# IsNoTeensy_v1_0.net
KiCad netlist of a schematic drawn in EAGLE
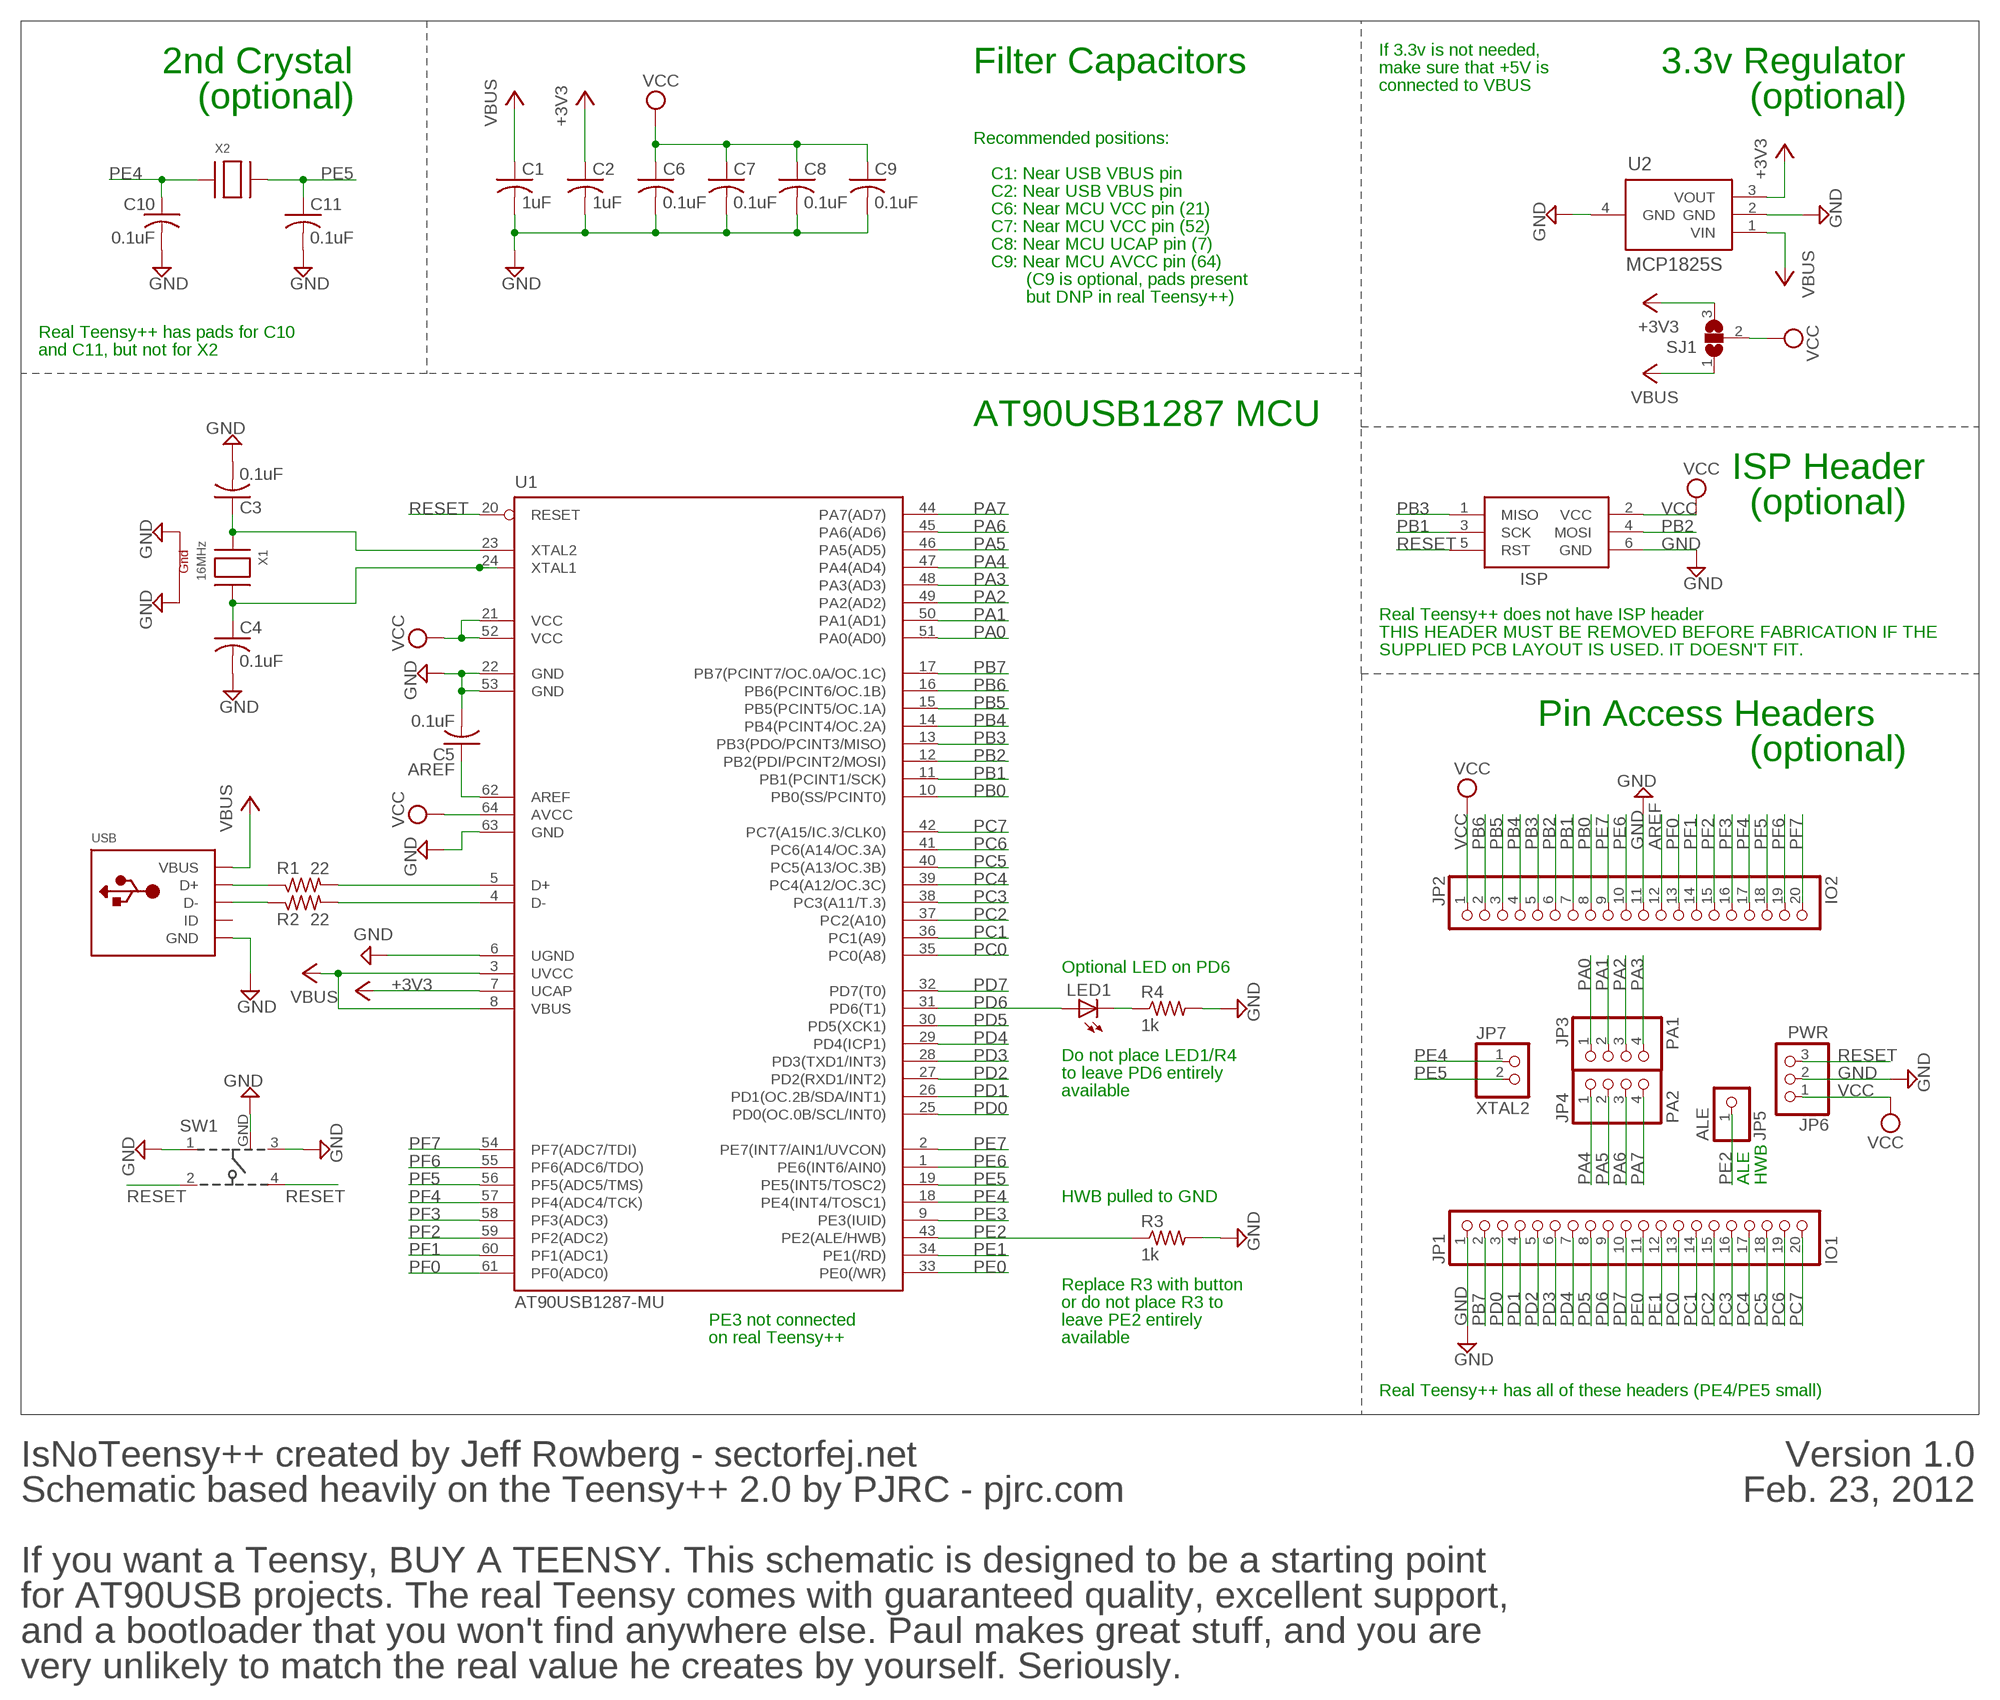
[diagram p0: schematic, sheet 1]

(export (version "E")
  (design (tool "Eeschema 10.0.6"))
  (components
    (comp (ref "C1")
      (value "1uF")
      (footprint "eagle-import:C0603")
      (libsource (lib "eagle-import") (part "C-USC0603"))
    )
    (comp (ref "C2")
      (value "1uF")
      (footprint "eagle-import:C0603")
      (libsource (lib "eagle-import") (part "C-USC0603"))
    )
    (comp (ref "C3")
      (value "0.1uF")
      (footprint "eagle-import:C0402")
      (libsource (lib "eagle-import") (part "C-USC0402"))
    )
    (comp (ref "C4")
      (value "0.1uF")
      (footprint "eagle-import:C0402")
      (libsource (lib "eagle-import") (part "C-USC0402"))
    )
    (comp (ref "C5")
      (value "0.1uF")
      (footprint "eagle-import:C0402")
      (libsource (lib "eagle-import") (part "C-USC0402"))
    )
    (comp (ref "C6")
      (value "0.1uF")
      (footprint "eagle-import:C0402")
      (libsource (lib "eagle-import") (part "C-USC0402"))
    )
    (comp (ref "C7")
      (value "0.1uF")
      (footprint "eagle-import:C0402")
      (libsource (lib "eagle-import") (part "C-USC0402"))
    )
    (comp (ref "C8")
      (value "0.1uF")
      (footprint "eagle-import:C0402")
      (libsource (lib "eagle-import") (part "C-USC0402"))
    )
    (comp (ref "C9")
      (value "0.1uF")
      (footprint "eagle-import:C0805")
      (libsource (lib "eagle-import") (part "C-USC0805"))
    )
    (comp (ref "C10")
      (value "0.1uF")
      (footprint "eagle-import:C0805")
      (libsource (lib "eagle-import") (part "C-USC0805"))
    )
    (comp (ref "C11")
      (value "0.1uF")
      (footprint "eagle-import:C0805")
      (libsource (lib "eagle-import") (part "C-USC0805"))
    )
    (comp (ref "ISP")
      (value "AVRISP-6")
      (footprint "eagle-import:AVRISP")
      (libsource (lib "eagle-import") (part "AVRISP-6"))
    )
    (comp (ref "JP1")
      (value "IO1")
      (footprint "eagle-import:1X20")
      (libsource (lib "eagle-import") (part "PINHD-1X20"))
    )
    (comp (ref "JP2")
      (value "IO2")
      (footprint "eagle-import:1X20")
      (libsource (lib "eagle-import") (part "PINHD-1X20"))
    )
    (comp (ref "JP3")
      (value "PA1")
      (footprint "eagle-import:1X04")
      (libsource (lib "eagle-import") (part "PINHD-1X4"))
    )
    (comp (ref "JP4")
      (value "PA2")
      (footprint "eagle-import:1X04")
      (libsource (lib "eagle-import") (part "PINHD-1X4"))
    )
    (comp (ref "JP5")
      (value "ALE")
      (footprint "eagle-import:1X01")
      (libsource (lib "eagle-import") (part "PINHD-1X1"))
    )
    (comp (ref "JP6")
      (value "PWR")
      (footprint "eagle-import:1X03")
      (libsource (lib "eagle-import") (part "PINHD-1X3"))
    )
    (comp (ref "JP7")
      (value "XTAL2")
      (footprint "eagle-import:1X02")
      (libsource (lib "eagle-import") (part "PINHD-1X2"))
    )
    (comp (ref "LED1")
      (value "LEDCHIP-LED0603")
      (footprint "eagle-import:CHIP-LED0603")
      (libsource (lib "eagle-import") (part "LEDCHIP-LED0603"))
    )
    (comp (ref "R1")
      (value "22")
      (footprint "eagle-import:R0402")
      (libsource (lib "eagle-import") (part "R-US_R0402"))
    )
    (comp (ref "R2")
      (value "22")
      (footprint "eagle-import:R0402")
      (libsource (lib "eagle-import") (part "R-US_R0402"))
    )
    (comp (ref "R3")
      (value "1k")
      (footprint "eagle-import:R0402")
      (libsource (lib "eagle-import") (part "R-US_R0402"))
    )
    (comp (ref "R4")
      (value "1k")
      (footprint "eagle-import:R0402")
      (libsource (lib "eagle-import") (part "R-US_R0402"))
    )
    (comp (ref "SJ1")
      (value "SJ2W")
      (footprint "eagle-import:SJ_2")
      (libsource (lib "eagle-import") (part "SJ2W"))
    )
    (comp (ref "SW1")
      (value "101-IG")
      (footprint "eagle-import:101-IG")
      (libsource (lib "eagle-import") (part "101-IG"))
    )
    (comp (ref "U1")
      (value "AT90USB1287-MU")
      (footprint "eagle-import:MLF64")
      (libsource (lib "eagle-import") (part "AT90USB1287-MU"))
    )
    (comp (ref "U2")
      (value "MCP1825S")
      (footprint "eagle-import:SOT223")
      (libsource (lib "eagle-import") (part "MCP1825S"))
    )
    (comp (ref "USB")
      (value "USBMINIB")
      (footprint "eagle-import:USB-MINIB")
      (libsource (lib "eagle-import") (part "USBMINIB"))
    )
    (comp (ref "X1")
      (value "16MHz")
      (footprint "eagle-import:NX3225")
      (libsource (lib "eagle-import") (part "XTAL-4-3225"))
    )
    (comp (ref "X2")
      (value "XTAL-3.2X1.5")
      (footprint "eagle-import:XTAL3215")
      (libsource (lib "eagle-import") (part "XTAL-3.2X1.5"))
    )
  )
  (nets
    (net (code "1") (name "+3V3") (class "Default")
      (node (ref "C2") (pin "1") (pinfunction "1_1") (pintype "passive"))
      (node (ref "SJ1") (pin "3") (pinfunction "3_3") (pintype "passive"))
      (node (ref "U1") (pin "7") (pinfunction "UCAP_7") (pintype "power_in"))
      (node (ref "U2") (pin "3") (pinfunction "VOUT_3") (pintype "power_in"))
    )
    (net (code "2") (name "/AREF") (class "Default")
      (node (ref "C5") (pin "1") (pinfunction "1_1") (pintype "passive"))
      (node (ref "JP2") (pin "12") (pinfunction "12_12") (pintype "passive"))
      (node (ref "U1") (pin "62") (pinfunction "AREF_62") (pintype "bidirectional"))
    )
    (net (code "3") (name "/PA0") (class "Default")
      (node (ref "JP3") (pin "1") (pinfunction "1_1") (pintype "passive"))
      (node (ref "U1") (pin "51") (pinfunction "PA0(AD0)_51") (pintype "bidirectional"))
    )
    (net (code "4") (name "/PA1") (class "Default")
      (node (ref "JP3") (pin "2") (pinfunction "2_2") (pintype "passive"))
      (node (ref "U1") (pin "50") (pinfunction "PA1(AD1)_50") (pintype "bidirectional"))
    )
    (net (code "5") (name "/PA2") (class "Default")
      (node (ref "JP3") (pin "3") (pinfunction "3_3") (pintype "passive"))
      (node (ref "U1") (pin "49") (pinfunction "PA2(AD2)_49") (pintype "bidirectional"))
    )
    (net (code "6") (name "/PA3") (class "Default")
      (node (ref "JP3") (pin "4") (pinfunction "4_4") (pintype "passive"))
      (node (ref "U1") (pin "48") (pinfunction "PA3(AD3)_48") (pintype "bidirectional"))
    )
    (net (code "7") (name "/PA4") (class "Default")
      (node (ref "JP4") (pin "1") (pinfunction "1_1") (pintype "passive"))
      (node (ref "U1") (pin "47") (pinfunction "PA4(AD4)_47") (pintype "bidirectional"))
    )
    (net (code "8") (name "/PA5") (class "Default")
      (node (ref "JP4") (pin "2") (pinfunction "2_2") (pintype "passive"))
      (node (ref "U1") (pin "46") (pinfunction "PA5(AD5)_46") (pintype "bidirectional"))
    )
    (net (code "9") (name "/PA6") (class "Default")
      (node (ref "JP4") (pin "3") (pinfunction "3_3") (pintype "passive"))
      (node (ref "U1") (pin "45") (pinfunction "PA6(AD6)_45") (pintype "bidirectional"))
    )
    (net (code "10") (name "/PA7") (class "Default")
      (node (ref "JP4") (pin "4") (pinfunction "4_4") (pintype "passive"))
      (node (ref "U1") (pin "44") (pinfunction "PA7(AD7)_44") (pintype "bidirectional"))
    )
    (net (code "11") (name "/PB0") (class "Default")
      (node (ref "JP2") (pin "8") (pinfunction "8_8") (pintype "passive"))
      (node (ref "U1") (pin "10") (pinfunction "PB0(SS/PCINT0)_10") (pintype "bidirectional"))
    )
    (net (code "12") (name "/PB1") (class "Default")
      (node (ref "ISP") (pin "3") (pinfunction "SCK_3") (pintype "output"))
      (node (ref "JP2") (pin "7") (pinfunction "7_7") (pintype "passive"))
      (node (ref "U1") (pin "11") (pinfunction "PB1(PCINT1/SCK)_11") (pintype "bidirectional"))
    )
    (net (code "13") (name "/PB2") (class "Default")
      (node (ref "ISP") (pin "4") (pinfunction "MOSI_4") (pintype "output"))
      (node (ref "JP2") (pin "6") (pinfunction "6_6") (pintype "passive"))
      (node (ref "U1") (pin "12") (pinfunction "PB2(PDI/PCINT2/MOSI)_12") (pintype "bidirectional"))
    )
    (net (code "14") (name "/PB3") (class "Default")
      (node (ref "ISP") (pin "1") (pinfunction "MISO_1") (pintype "input"))
      (node (ref "JP2") (pin "5") (pinfunction "5_5") (pintype "passive"))
      (node (ref "U1") (pin "13") (pinfunction "PB3(PDO/PCINT3/MISO)_13") (pintype "bidirectional"))
    )
    (net (code "15") (name "/PB4") (class "Default")
      (node (ref "JP2") (pin "4") (pinfunction "4_4") (pintype "passive"))
      (node (ref "U1") (pin "14") (pinfunction "PB4(PCINT4/OC.2A)_14") (pintype "bidirectional"))
    )
    (net (code "16") (name "/PB5") (class "Default")
      (node (ref "JP2") (pin "3") (pinfunction "3_3") (pintype "passive"))
      (node (ref "U1") (pin "15") (pinfunction "PB5(PCINT5/OC.1A)_15") (pintype "bidirectional"))
    )
    (net (code "17") (name "/PB6") (class "Default")
      (node (ref "JP2") (pin "2") (pinfunction "2_2") (pintype "passive"))
      (node (ref "U1") (pin "16") (pinfunction "PB6(PCINT6/OC.1B)_16") (pintype "bidirectional"))
    )
    (net (code "18") (name "/PB7") (class "Default")
      (node (ref "JP1") (pin "2") (pinfunction "2_2") (pintype "passive"))
      (node (ref "U1") (pin "17") (pinfunction "PB7(PCINT7/OC.0A/OC.1C)_17") (pintype "bidirectional"))
    )
    (net (code "19") (name "/PC0") (class "Default")
      (node (ref "JP1") (pin "13") (pinfunction "13_13") (pintype "passive"))
      (node (ref "U1") (pin "35") (pinfunction "PC0(A8)_35") (pintype "bidirectional"))
    )
    (net (code "20") (name "/PC1") (class "Default")
      (node (ref "JP1") (pin "14") (pinfunction "14_14") (pintype "passive"))
      (node (ref "U1") (pin "36") (pinfunction "PC1(A9)_36") (pintype "bidirectional"))
    )
    (net (code "21") (name "/PC2") (class "Default")
      (node (ref "JP1") (pin "15") (pinfunction "15_15") (pintype "passive"))
      (node (ref "U1") (pin "37") (pinfunction "PC2(A10)_37") (pintype "bidirectional"))
    )
    (net (code "22") (name "/PC3") (class "Default")
      (node (ref "JP1") (pin "16") (pinfunction "16_16") (pintype "passive"))
      (node (ref "U1") (pin "38") (pinfunction "PC3(A11/T.3)_38") (pintype "bidirectional"))
    )
    (net (code "23") (name "/PC4") (class "Default")
      (node (ref "JP1") (pin "17") (pinfunction "17_17") (pintype "passive"))
      (node (ref "U1") (pin "39") (pinfunction "PC4(A12/OC.3C)_39") (pintype "bidirectional"))
    )
    (net (code "24") (name "/PC5") (class "Default")
      (node (ref "JP1") (pin "18") (pinfunction "18_18") (pintype "passive"))
      (node (ref "U1") (pin "40") (pinfunction "PC5(A13/OC.3B)_40") (pintype "bidirectional"))
    )
    (net (code "25") (name "/PC6") (class "Default")
      (node (ref "JP1") (pin "19") (pinfunction "19_19") (pintype "passive"))
      (node (ref "U1") (pin "41") (pinfunction "PC6(A14/OC.3A)_41") (pintype "bidirectional"))
    )
    (net (code "26") (name "/PC7") (class "Default")
      (node (ref "JP1") (pin "20") (pinfunction "20_20") (pintype "passive"))
      (node (ref "U1") (pin "42") (pinfunction "PC7(A15/IC.3/CLK0)_42") (pintype "bidirectional"))
    )
    (net (code "27") (name "/PD0") (class "Default")
      (node (ref "JP1") (pin "3") (pinfunction "3_3") (pintype "passive"))
      (node (ref "U1") (pin "25") (pinfunction "PD0(OC.0B/SCL/INT0)_25") (pintype "bidirectional"))
    )
    (net (code "28") (name "/PD1") (class "Default")
      (node (ref "JP1") (pin "4") (pinfunction "4_4") (pintype "passive"))
      (node (ref "U1") (pin "26") (pinfunction "PD1(OC.2B/SDA/INT1)_26") (pintype "bidirectional"))
    )
    (net (code "29") (name "/PD2") (class "Default")
      (node (ref "JP1") (pin "5") (pinfunction "5_5") (pintype "passive"))
      (node (ref "U1") (pin "27") (pinfunction "PD2(RXD1/INT2)_27") (pintype "bidirectional"))
    )
    (net (code "30") (name "/PD3") (class "Default")
      (node (ref "JP1") (pin "6") (pinfunction "6_6") (pintype "passive"))
      (node (ref "U1") (pin "28") (pinfunction "PD3(TXD1/INT3)_28") (pintype "bidirectional"))
    )
    (net (code "31") (name "/PD4") (class "Default")
      (node (ref "JP1") (pin "7") (pinfunction "7_7") (pintype "passive"))
      (node (ref "U1") (pin "29") (pinfunction "PD4(ICP1)_29") (pintype "bidirectional"))
    )
    (net (code "32") (name "/PD5") (class "Default")
      (node (ref "JP1") (pin "8") (pinfunction "8_8") (pintype "passive"))
      (node (ref "U1") (pin "30") (pinfunction "PD5(XCK1)_30") (pintype "bidirectional"))
    )
    (net (code "33") (name "/PD6") (class "Default")
      (node (ref "JP1") (pin "9") (pinfunction "9_9") (pintype "passive"))
      (node (ref "LED1") (pin "A") (pinfunction "A_A") (pintype "passive"))
      (node (ref "U1") (pin "31") (pinfunction "PD6(T1)_31") (pintype "bidirectional"))
    )
    (net (code "34") (name "/PD7") (class "Default")
      (node (ref "JP1") (pin "10") (pinfunction "10_10") (pintype "passive"))
      (node (ref "U1") (pin "32") (pinfunction "PD7(T0)_32") (pintype "bidirectional"))
    )
    (net (code "35") (name "/PE0") (class "Default")
      (node (ref "JP1") (pin "11") (pinfunction "11_11") (pintype "passive"))
      (node (ref "U1") (pin "33") (pinfunction "PE0(/WR)_33") (pintype "bidirectional"))
    )
    (net (code "36") (name "/PE1") (class "Default")
      (node (ref "JP1") (pin "12") (pinfunction "12_12") (pintype "passive"))
      (node (ref "U1") (pin "34") (pinfunction "PE1(/RD)_34") (pintype "bidirectional"))
    )
    (net (code "37") (name "/PE2") (class "Default")
      (node (ref "JP5") (pin "1") (pinfunction "1_1") (pintype "passive"))
      (node (ref "R3") (pin "1") (pinfunction "1_1") (pintype "passive"))
      (node (ref "U1") (pin "43") (pinfunction "PE2(ALE/HWB)_43") (pintype "bidirectional"))
    )
    (net (code "38") (name "/PE3") (class "Default")
      (node (ref "U1") (pin "9") (pinfunction "PE3(IUID)_9") (pintype "bidirectional"))
    )
    (net (code "39") (name "/PE4") (class "Default")
      (node (ref "C10") (pin "1") (pinfunction "1_1") (pintype "passive"))
      (node (ref "JP7") (pin "1") (pinfunction "1_1") (pintype "passive"))
      (node (ref "U1") (pin "18") (pinfunction "PE4(INT4/TOSC1)_18") (pintype "bidirectional"))
      (node (ref "X2") (pin "P$1") (pinfunction "P$1_P$1") (pintype "bidirectional"))
    )
    (net (code "40") (name "/PE5") (class "Default")
      (node (ref "C11") (pin "1") (pinfunction "1_1") (pintype "passive"))
      (node (ref "JP7") (pin "2") (pinfunction "2_2") (pintype "passive"))
      (node (ref "U1") (pin "19") (pinfunction "PE5(INT5/TOSC2)_19") (pintype "bidirectional"))
      (node (ref "X2") (pin "P$2") (pinfunction "P$2_P$2") (pintype "bidirectional"))
    )
    (net (code "41") (name "/PE6") (class "Default")
      (node (ref "JP2") (pin "10") (pinfunction "10_10") (pintype "passive"))
      (node (ref "U1") (pin "1") (pinfunction "PE6(INT6/AIN0)_1") (pintype "bidirectional"))
    )
    (net (code "42") (name "/PE7") (class "Default")
      (node (ref "JP2") (pin "9") (pinfunction "9_9") (pintype "passive"))
      (node (ref "U1") (pin "2") (pinfunction "PE7(INT7/AIN1/UVCON)_2") (pintype "bidirectional"))
    )
    (net (code "43") (name "/PF0") (class "Default")
      (node (ref "JP2") (pin "13") (pinfunction "13_13") (pintype "passive"))
      (node (ref "U1") (pin "61") (pinfunction "PF0(ADC0)_61") (pintype "bidirectional"))
    )
    (net (code "44") (name "/PF1") (class "Default")
      (node (ref "JP2") (pin "14") (pinfunction "14_14") (pintype "passive"))
      (node (ref "U1") (pin "60") (pinfunction "PF1(ADC1)_60") (pintype "bidirectional"))
    )
    (net (code "45") (name "/PF2") (class "Default")
      (node (ref "JP2") (pin "15") (pinfunction "15_15") (pintype "passive"))
      (node (ref "U1") (pin "59") (pinfunction "PF2(ADC2)_59") (pintype "bidirectional"))
    )
    (net (code "46") (name "/PF3") (class "Default")
      (node (ref "JP2") (pin "16") (pinfunction "16_16") (pintype "passive"))
      (node (ref "U1") (pin "58") (pinfunction "PF3(ADC3)_58") (pintype "bidirectional"))
    )
    (net (code "47") (name "/PF4") (class "Default")
      (node (ref "JP2") (pin "17") (pinfunction "17_17") (pintype "passive"))
      (node (ref "U1") (pin "57") (pinfunction "PF4(ADC4/TCK)_57") (pintype "bidirectional"))
    )
    (net (code "48") (name "/PF5") (class "Default")
      (node (ref "JP2") (pin "18") (pinfunction "18_18") (pintype "passive"))
      (node (ref "U1") (pin "56") (pinfunction "PF5(ADC5/TMS)_56") (pintype "bidirectional"))
    )
    (net (code "49") (name "/PF6") (class "Default")
      (node (ref "JP2") (pin "19") (pinfunction "19_19") (pintype "passive"))
      (node (ref "U1") (pin "55") (pinfunction "PF6(ADC6/TDO)_55") (pintype "bidirectional"))
    )
    (net (code "50") (name "/PF7") (class "Default")
      (node (ref "JP2") (pin "20") (pinfunction "20_20") (pintype "passive"))
      (node (ref "U1") (pin "54") (pinfunction "PF7(ADC7/TDI)_54") (pintype "bidirectional"))
    )
    (net (code "51") (name "/RESET") (class "Default")
      (node (ref "ISP") (pin "5") (pinfunction "RST_5") (pintype "output"))
      (node (ref "JP6") (pin "3") (pinfunction "3_3") (pintype "passive"))
      (node (ref "SW1") (pin "2") (pinfunction "2_2") (pintype "bidirectional"))
      (node (ref "SW1") (pin "4") (pinfunction "4_4") (pintype "bidirectional"))
      (node (ref "U1") (pin "20") (pinfunction "RESET_20") (pintype "input"))
    )
    (net (code "52") (name "GND") (class "Default")
      (node (ref "C1") (pin "2") (pinfunction "2_2") (pintype "passive"))
      (node (ref "C10") (pin "2") (pinfunction "2_2") (pintype "passive"))
      (node (ref "C11") (pin "2") (pinfunction "2_2") (pintype "passive"))
      (node (ref "C2") (pin "2") (pinfunction "2_2") (pintype "passive"))
      (node (ref "C3") (pin "2") (pinfunction "2_2") (pintype "passive"))
      (node (ref "C4") (pin "2") (pinfunction "2_2") (pintype "passive"))
      (node (ref "C5") (pin "2") (pinfunction "2_2") (pintype "passive"))
      (node (ref "C6") (pin "2") (pinfunction "2_2") (pintype "passive"))
      (node (ref "C7") (pin "2") (pinfunction "2_2") (pintype "passive"))
      (node (ref "C8") (pin "2") (pinfunction "2_2") (pintype "passive"))
      (node (ref "C9") (pin "2") (pinfunction "2_2") (pintype "passive"))
      (node (ref "ISP") (pin "6") (pinfunction "GND_6") (pintype "power_in"))
      (node (ref "JP1") (pin "1") (pinfunction "1_1") (pintype "passive"))
      (node (ref "JP2") (pin "11") (pinfunction "11_11") (pintype "passive"))
      (node (ref "JP6") (pin "2") (pinfunction "2_2") (pintype "passive"))
      (node (ref "R3") (pin "2") (pinfunction "2_2") (pintype "passive"))
      (node (ref "R4") (pin "2") (pinfunction "2_2") (pintype "passive"))
      (node (ref "SW1") (pin "1") (pinfunction "1_1") (pintype "bidirectional"))
      (node (ref "SW1") (pin "3") (pinfunction "3_3") (pintype "bidirectional"))
      (node (ref "SW1") (pin "GND") (pinfunction "GND_GND") (pintype "power_in"))
      (node (ref "U1") (pin "22") (pinfunction "GND_22") (pintype "power_in"))
      (node (ref "U1") (pin "53") (pinfunction "GND_53") (pintype "power_in"))
      (node (ref "U1") (pin "6") (pinfunction "UGND_6") (pintype "power_in"))
      (node (ref "U1") (pin "63") (pinfunction "GND_63") (pintype "power_in"))
      (node (ref "U2") (pin "2") (pinfunction "GND_2") (pintype "power_in"))
      (node (ref "U2") (pin "4") (pinfunction "GND_4") (pintype "power_in"))
      (node (ref "USB") (pin "GND") (pinfunction "GND_GND") (pintype "power_in"))
      (node (ref "USB") (pin "GND1") (pinfunction "GND_GND1") (pintype "power_in"))
      (node (ref "USB") (pin "GND2") (pinfunction "GND_GND2") (pintype "power_in"))
      (node (ref "USB") (pin "GND3") (pinfunction "GND_GND3") (pintype "power_in"))
      (node (ref "USB") (pin "GND4") (pinfunction "GND_GND4") (pintype "power_in"))
      (node (ref "X1") (pin "2") (pinfunction "G1_2") (pintype "power_in"))
      (node (ref "X1") (pin "4") (pinfunction "G2_4") (pintype "power_in"))
    )
    (net (code "53") (name "Net-(LED1-PadC)") (class "Default")
      (node (ref "LED1") (pin "C") (pinfunction "C_C") (pintype "passive"))
      (node (ref "R4") (pin "1") (pinfunction "1_1") (pintype "passive"))
    )
    (net (code "54") (name "Net-(R1-Pad1)") (class "Default")
      (node (ref "R1") (pin "1") (pinfunction "1_1") (pintype "passive"))
      (node (ref "USB") (pin "D+") (pinfunction "D+_D+") (pintype "bidirectional"))
    )
    (net (code "55") (name "Net-(R2-Pad1)") (class "Default")
      (node (ref "R2") (pin "1") (pinfunction "1_1") (pintype "passive"))
      (node (ref "USB") (pin "D-") (pinfunction "D-_D-") (pintype "bidirectional"))
    )
    (net (code "56") (name "Net-(U1-D+)") (class "Default")
      (node (ref "R1") (pin "2") (pinfunction "2_2") (pintype "passive"))
      (node (ref "U1") (pin "5") (pinfunction "D+_5") (pintype "bidirectional"))
    )
    (net (code "57") (name "Net-(U1-D-)") (class "Default")
      (node (ref "R2") (pin "2") (pinfunction "2_2") (pintype "passive"))
      (node (ref "U1") (pin "4") (pinfunction "D-_4") (pintype "bidirectional"))
    )
    (net (code "58") (name "Net-(U1-XTAL1)") (class "Default")
      (node (ref "C4") (pin "1") (pinfunction "1_1") (pintype "passive"))
      (node (ref "U1") (pin "24") (pinfunction "XTAL1_24") (pintype "bidirectional"))
      (node (ref "X1") (pin "3") (pinfunction "X2_3") (pintype "bidirectional"))
    )
    (net (code "59") (name "Net-(U1-XTAL2)") (class "Default")
      (node (ref "C3") (pin "1") (pinfunction "1_1") (pintype "passive"))
      (node (ref "U1") (pin "23") (pinfunction "XTAL2_23") (pintype "bidirectional"))
      (node (ref "X1") (pin "1") (pinfunction "X1_1") (pintype "bidirectional"))
    )
    (net (code "60") (name "VBUS") (class "Default")
      (node (ref "C1") (pin "1") (pinfunction "1_1") (pintype "passive"))
      (node (ref "SJ1") (pin "1") (pinfunction "1_1") (pintype "passive"))
      (node (ref "U1") (pin "3") (pinfunction "UVCC_3") (pintype "power_in"))
      (node (ref "U1") (pin "8") (pinfunction "VBUS_8") (pintype "power_in"))
      (node (ref "U2") (pin "1") (pinfunction "VIN_1") (pintype "power_in"))
      (node (ref "USB") (pin "VBUS") (pinfunction "VBUS_VBUS") (pintype "power_in"))
    )
    (net (code "61") (name "VCC") (class "Default")
      (node (ref "C6") (pin "1") (pinfunction "1_1") (pintype "passive"))
      (node (ref "C7") (pin "1") (pinfunction "1_1") (pintype "passive"))
      (node (ref "C8") (pin "1") (pinfunction "1_1") (pintype "passive"))
      (node (ref "C9") (pin "1") (pinfunction "1_1") (pintype "passive"))
      (node (ref "ISP") (pin "2") (pinfunction "VCC_2") (pintype "power_in"))
      (node (ref "JP2") (pin "1") (pinfunction "1_1") (pintype "passive"))
      (node (ref "JP6") (pin "1") (pinfunction "1_1") (pintype "passive"))
      (node (ref "SJ1") (pin "2") (pinfunction "2_2") (pintype "passive"))
      (node (ref "U1") (pin "21") (pinfunction "VCC_21") (pintype "power_in"))
      (node (ref "U1") (pin "52") (pinfunction "VCC_52") (pintype "power_in"))
      (node (ref "U1") (pin "64") (pinfunction "AVCC_64") (pintype "bidirectional"))
    )
    (net (code "62") (name "unconnected-(USB-PadID)") (class "Default")
      (node (ref "USB") (pin "ID") (pinfunction "ID_ID") (pintype "bidirectional"))
    )
  )
)
